# bridge.net
KiCad netlist of a schematic drawn in EAGLE
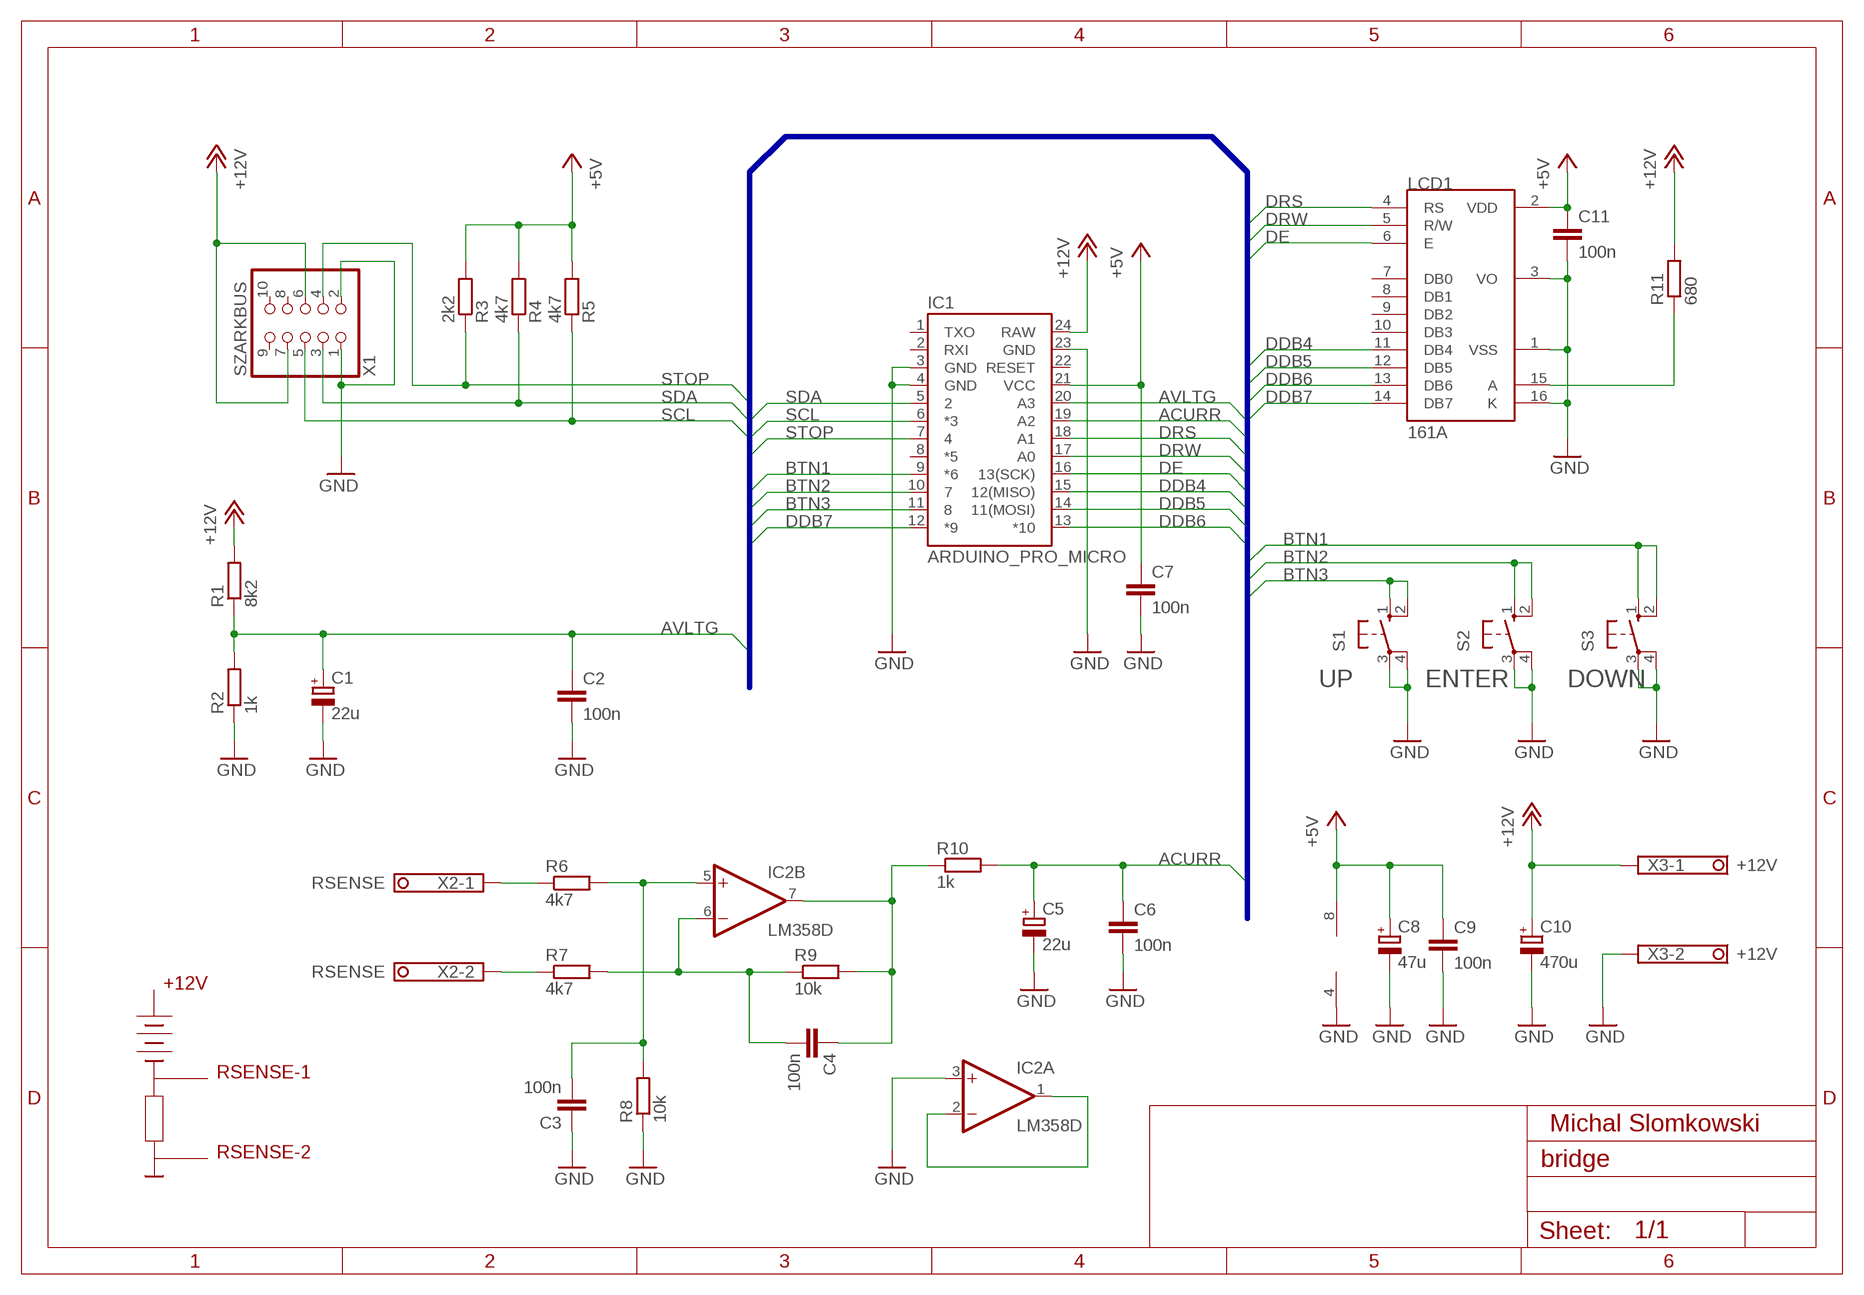
[diagram p0: schematic, sheet 1]

(export (version "E")
  (design (tool "Eeschema 10.0.6"))
  (components
    (comp (ref "C1")
      (value "22u")
      (footprint "eagle-import:B_3528-21W")
      (libsource (lib "eagle-import") (part "CPOL-EUB/3528-21W"))
    )
    (comp (ref "C2")
      (value "100n")
      (footprint "eagle-import:C1206")
      (libsource (lib "eagle-import") (part "C-EUC1206"))
    )
    (comp (ref "C3")
      (value "100n")
      (footprint "eagle-import:C1210")
      (libsource (lib "eagle-import") (part "C-EUC1210"))
    )
    (comp (ref "C4")
      (value "100n")
      (footprint "eagle-import:C1206")
      (libsource (lib "eagle-import") (part "C-EUC1206"))
    )
    (comp (ref "C5")
      (value "22u")
      (footprint "eagle-import:B_3528-21W")
      (libsource (lib "eagle-import") (part "CPOL-EUB/3528-21W"))
    )
    (comp (ref "C6")
      (value "100n")
      (footprint "eagle-import:C1206")
      (libsource (lib "eagle-import") (part "C-EUC1206"))
    )
    (comp (ref "C7")
      (value "100n")
      (footprint "eagle-import:C1206")
      (libsource (lib "eagle-import") (part "C-EUC1206"))
    )
    (comp (ref "C8")
      (value "47u")
      (footprint "eagle-import:C_6032-28W")
      (libsource (lib "eagle-import") (part "CPOL-EUC/6032-28W"))
    )
    (comp (ref "C9")
      (value "100n")
      (footprint "eagle-import:C1206")
      (libsource (lib "eagle-import") (part "C-EUC1206"))
    )
    (comp (ref "C10")
      (value "470u")
      (footprint "eagle-import:E5-8,5")
      (libsource (lib "eagle-import") (part "CPOL-EUE5-8.5"))
    )
    (comp (ref "C11")
      (value "100n")
      (footprint "eagle-import:C1206")
      (libsource (lib "eagle-import") (part "C-EUC1206"))
    )
    (comp (ref "IC1")
      (value "ARDUINO_PRO_MICRO")
      (footprint "eagle-import:ARDUINO_PRO_MICRO")
      (libsource (lib "eagle-import") (part "ARDUINO_PRO_MICRO"))
    )
    (comp (ref "IC2")
      (value "LM358D")
      (footprint "eagle-import:SO08")
      (libsource (lib "eagle-import") (part "LM358D"))
    )
    (comp (ref "LCD1")
      (value "161A")
      (footprint "eagle-import:161A")
      (libsource (lib "eagle-import") (part "161A"))
    )
    (comp (ref "R1")
      (value "8k2")
      (footprint "eagle-import:M1206")
      (libsource (lib "eagle-import") (part "R-EU_M1206"))
    )
    (comp (ref "R2")
      (value "1k")
      (footprint "eagle-import:M1206")
      (libsource (lib "eagle-import") (part "R-EU_M1206"))
    )
    (comp (ref "R3")
      (value "2k2")
      (footprint "eagle-import:M1206")
      (libsource (lib "eagle-import") (part "R-EU_M1206"))
    )
    (comp (ref "R4")
      (value "4k7")
      (footprint "eagle-import:M1206")
      (libsource (lib "eagle-import") (part "R-EU_M1206"))
    )
    (comp (ref "R5")
      (value "4k7")
      (footprint "eagle-import:M1206")
      (libsource (lib "eagle-import") (part "R-EU_M1206"))
    )
    (comp (ref "R6")
      (value "4k7")
      (footprint "eagle-import:M1206")
      (libsource (lib "eagle-import") (part "R-EU_M1206"))
    )
    (comp (ref "R7")
      (value "4k7")
      (footprint "eagle-import:M1206")
      (libsource (lib "eagle-import") (part "R-EU_M1206"))
    )
    (comp (ref "R8")
      (value "10k")
      (footprint "eagle-import:M1206")
      (libsource (lib "eagle-import") (part "R-EU_M1206"))
    )
    (comp (ref "R9")
      (value "10k")
      (footprint "eagle-import:M1206")
      (libsource (lib "eagle-import") (part "R-EU_M1206"))
    )
    (comp (ref "R10")
      (value "1k")
      (footprint "eagle-import:M1206")
      (libsource (lib "eagle-import") (part "R-EU_M1206"))
    )
    (comp (ref "R11")
      (value "680")
      (footprint "eagle-import:0207_12")
      (libsource (lib "eagle-import") (part "R-EU_0207/12"))
    )
    (comp (ref "S1")
      (value "10-XX")
      (footprint "eagle-import:B3F-10XX")
      (fields (field (name "MPN") "B3F-1000"))
      (libsource (lib "eagle-import") (part "10-XX"))
    )
    (comp (ref "S2")
      (value "10-XX")
      (footprint "eagle-import:B3F-10XX")
      (fields (field (name "MPN") "B3F-1000"))
      (libsource (lib "eagle-import") (part "10-XX"))
    )
    (comp (ref "S3")
      (value "10-XX")
      (footprint "eagle-import:B3F-10XX")
      (fields (field (name "MPN") "B3F-1000"))
      (libsource (lib "eagle-import") (part "10-XX"))
    )
    (comp (ref "X1")
      (value "SZARKBUS")
      (footprint "eagle-import:2X05")
      (libsource (lib "eagle-import") (part "PINHD-2X5"))
    )
    (comp (ref "X2")
      (value "RSENSE")
      (footprint "eagle-import:1751248")
      (libsource (lib "eagle-import") (part "1751248"))
    )
    (comp (ref "X3")
      (value "+12V")
      (footprint "eagle-import:1751248")
      (libsource (lib "eagle-import") (part "1751248"))
    )
  )
  (nets
    (net (code "1") (name "+5V") (class "Default")
      (node (ref "C11") (pin "1") (pinfunction "1_1") (pintype "passive"))
      (node (ref "C7") (pin "1") (pinfunction "1_1") (pintype "passive"))
      (node (ref "C8") (pin "+") (pinfunction "+_+") (pintype "passive"))
      (node (ref "C9") (pin "1") (pinfunction "1_1") (pintype "passive"))
      (node (ref "IC1") (pin "21") (pinfunction "VCC_21") (pintype "bidirectional"))
      (node (ref "IC2") (pin "8") (pinfunction "V+_8") (pintype "power_in"))
      (node (ref "LCD1") (pin "2") (pinfunction "VDD_2") (pintype "power_in"))
      (node (ref "R3") (pin "2") (pinfunction "2_2") (pintype "passive"))
      (node (ref "R4") (pin "2") (pinfunction "2_2") (pintype "passive"))
      (node (ref "R5") (pin "2") (pinfunction "2_2") (pintype "passive"))
    )
    (net (code "2") (name "+12V") (class "Default")
      (node (ref "C10") (pin "+") (pinfunction "+_+") (pintype "passive"))
      (node (ref "IC1") (pin "24") (pinfunction "RAW_24") (pintype "bidirectional"))
      (node (ref "R1") (pin "2") (pinfunction "2_2") (pintype "passive"))
      (node (ref "R11") (pin "2") (pinfunction "2_2") (pintype "passive"))
      (node (ref "X1") (pin "6") (pinfunction "6_6") (pintype "passive"))
      (node (ref "X1") (pin "7") (pinfunction "7_7") (pintype "passive"))
      (node (ref "X3") (pin "1") (pinfunction "K_1") (pintype "passive"))
    )
    (net (code "3") (name "/ACURR") (class "Default")
      (node (ref "C5") (pin "+") (pinfunction "+_+") (pintype "passive"))
      (node (ref "C6") (pin "1") (pinfunction "1_1") (pintype "passive"))
      (node (ref "IC1") (pin "19") (pinfunction "A2_19") (pintype "bidirectional"))
      (node (ref "R10") (pin "2") (pinfunction "2_2") (pintype "passive"))
    )
    (net (code "4") (name "/AVLTG") (class "Default")
      (node (ref "C1") (pin "+") (pinfunction "+_+") (pintype "passive"))
      (node (ref "C2") (pin "1") (pinfunction "1_1") (pintype "passive"))
      (node (ref "IC1") (pin "20") (pinfunction "A3_20") (pintype "bidirectional"))
      (node (ref "R1") (pin "1") (pinfunction "1_1") (pintype "passive"))
      (node (ref "R2") (pin "2") (pinfunction "2_2") (pintype "passive"))
    )
    (net (code "5") (name "/BTN1") (class "Default")
      (node (ref "IC1") (pin "9") (pinfunction "*6_9") (pintype "bidirectional"))
      (node (ref "S3") (pin "1") (pinfunction "S_1") (pintype "passive"))
      (node (ref "S3") (pin "2") (pinfunction "S1_2") (pintype "passive"))
    )
    (net (code "6") (name "/BTN2") (class "Default")
      (node (ref "IC1") (pin "10") (pinfunction "7_10") (pintype "bidirectional"))
      (node (ref "S2") (pin "1") (pinfunction "S_1") (pintype "passive"))
      (node (ref "S2") (pin "2") (pinfunction "S1_2") (pintype "passive"))
    )
    (net (code "7") (name "/BTN3") (class "Default")
      (node (ref "IC1") (pin "11") (pinfunction "8_11") (pintype "bidirectional"))
      (node (ref "S1") (pin "1") (pinfunction "S_1") (pintype "passive"))
      (node (ref "S1") (pin "2") (pinfunction "S1_2") (pintype "passive"))
    )
    (net (code "8") (name "/DDB4") (class "Default")
      (node (ref "IC1") (pin "15") (pinfunction "12(MISO)_15") (pintype "bidirectional"))
      (node (ref "LCD1") (pin "11") (pinfunction "DB4_11") (pintype "bidirectional"))
    )
    (net (code "9") (name "/DDB5") (class "Default")
      (node (ref "IC1") (pin "14") (pinfunction "11(MOSI)_14") (pintype "bidirectional"))
      (node (ref "LCD1") (pin "12") (pinfunction "DB5_12") (pintype "bidirectional"))
    )
    (net (code "10") (name "/DDB6") (class "Default")
      (node (ref "IC1") (pin "13") (pinfunction "*10_13") (pintype "bidirectional"))
      (node (ref "LCD1") (pin "13") (pinfunction "DB6_13") (pintype "bidirectional"))
    )
    (net (code "11") (name "/DDB7") (class "Default")
      (node (ref "IC1") (pin "12") (pinfunction "*9_12") (pintype "bidirectional"))
      (node (ref "LCD1") (pin "14") (pinfunction "DB7_14") (pintype "bidirectional"))
    )
    (net (code "12") (name "/DE") (class "Default")
      (node (ref "IC1") (pin "16") (pinfunction "13(SCK)_16") (pintype "bidirectional"))
      (node (ref "LCD1") (pin "6") (pinfunction "E_6") (pintype "bidirectional"))
    )
    (net (code "13") (name "/DRS") (class "Default")
      (node (ref "IC1") (pin "18") (pinfunction "A1_18") (pintype "bidirectional"))
      (node (ref "LCD1") (pin "4") (pinfunction "RS_4") (pintype "bidirectional"))
    )
    (net (code "14") (name "/DRW") (class "Default")
      (node (ref "IC1") (pin "17") (pinfunction "A0_17") (pintype "bidirectional"))
      (node (ref "LCD1") (pin "5") (pinfunction "R/W_5") (pintype "bidirectional"))
    )
    (net (code "15") (name "/SCL") (class "Default")
      (node (ref "IC1") (pin "6") (pinfunction "*3_6") (pintype "bidirectional"))
      (node (ref "R5") (pin "1") (pinfunction "1_1") (pintype "passive"))
      (node (ref "X1") (pin "5") (pinfunction "5_5") (pintype "passive"))
    )
    (net (code "16") (name "/SDA") (class "Default")
      (node (ref "IC1") (pin "5") (pinfunction "2_5") (pintype "bidirectional"))
      (node (ref "R4") (pin "1") (pinfunction "1_1") (pintype "passive"))
      (node (ref "X1") (pin "3") (pinfunction "3_3") (pintype "passive"))
    )
    (net (code "17") (name "/STOP") (class "Default")
      (node (ref "IC1") (pin "7") (pinfunction "4_7") (pintype "bidirectional"))
      (node (ref "R3") (pin "1") (pinfunction "1_1") (pintype "passive"))
      (node (ref "X1") (pin "4") (pinfunction "4_4") (pintype "passive"))
    )
    (net (code "18") (name "GND") (class "Default")
      (node (ref "C1") (pin "-") (pinfunction "-_-") (pintype "passive"))
      (node (ref "C10") (pin "-") (pinfunction "-_-") (pintype "passive"))
      (node (ref "C11") (pin "2") (pinfunction "2_2") (pintype "passive"))
      (node (ref "C2") (pin "2") (pinfunction "2_2") (pintype "passive"))
      (node (ref "C3") (pin "1") (pinfunction "1_1") (pintype "passive"))
      (node (ref "C5") (pin "-") (pinfunction "-_-") (pintype "passive"))
      (node (ref "C6") (pin "2") (pinfunction "2_2") (pintype "passive"))
      (node (ref "C7") (pin "2") (pinfunction "2_2") (pintype "passive"))
      (node (ref "C8") (pin "-") (pinfunction "-_-") (pintype "passive"))
      (node (ref "C9") (pin "2") (pinfunction "2_2") (pintype "passive"))
      (node (ref "IC1") (pin "23") (pinfunction "GND_23") (pintype "bidirectional"))
      (node (ref "IC1") (pin "3") (pinfunction "GND_3") (pintype "bidirectional"))
      (node (ref "IC1") (pin "4") (pinfunction "GND_4") (pintype "bidirectional"))
      (node (ref "IC2") (pin "3") (pinfunction "+IN_3") (pintype "input"))
      (node (ref "IC2") (pin "4") (pinfunction "V-_4") (pintype "power_in"))
      (node (ref "LCD1") (pin "1") (pinfunction "VSS_1") (pintype "power_in"))
      (node (ref "LCD1") (pin "16") (pinfunction "K_16") (pintype "power_in"))
      (node (ref "LCD1") (pin "3") (pinfunction "VO_3") (pintype "input"))
      (node (ref "R2") (pin "1") (pinfunction "1_1") (pintype "passive"))
      (node (ref "R8") (pin "1") (pinfunction "1_1") (pintype "passive"))
      (node (ref "S1") (pin "3") (pinfunction "P_3") (pintype "passive"))
      (node (ref "S1") (pin "4") (pinfunction "P1_4") (pintype "passive"))
      (node (ref "S2") (pin "3") (pinfunction "P_3") (pintype "passive"))
      (node (ref "S2") (pin "4") (pinfunction "P1_4") (pintype "passive"))
      (node (ref "S3") (pin "3") (pinfunction "P_3") (pintype "passive"))
      (node (ref "S3") (pin "4") (pinfunction "P1_4") (pintype "passive"))
      (node (ref "X1") (pin "1") (pinfunction "1_1") (pintype "passive"))
      (node (ref "X1") (pin "2") (pinfunction "2_2") (pintype "passive"))
      (node (ref "X3") (pin "2") (pinfunction "K_2") (pintype "passive"))
    )
    (net (code "19") (name "Net-(IC2A--IN)") (class "Default")
      (node (ref "IC2") (pin "1") (pinfunction "OUT_1") (pintype "output"))
      (node (ref "IC2") (pin "2") (pinfunction "-IN_2") (pintype "input"))
    )
    (net (code "20") (name "Net-(IC2B-+IN)") (class "Default")
      (node (ref "C3") (pin "2") (pinfunction "2_2") (pintype "passive"))
      (node (ref "IC2") (pin "5") (pinfunction "+IN_5") (pintype "input"))
      (node (ref "R6") (pin "2") (pinfunction "2_2") (pintype "passive"))
      (node (ref "R8") (pin "2") (pinfunction "2_2") (pintype "passive"))
    )
    (net (code "21") (name "Net-(IC2B--IN)") (class "Default")
      (node (ref "C4") (pin "2") (pinfunction "2_2") (pintype "passive"))
      (node (ref "IC2") (pin "6") (pinfunction "-IN_6") (pintype "input"))
      (node (ref "R7") (pin "2") (pinfunction "2_2") (pintype "passive"))
      (node (ref "R9") (pin "1") (pinfunction "1_1") (pintype "passive"))
    )
    (net (code "22") (name "Net-(IC2B-OUT)") (class "Default")
      (node (ref "C4") (pin "1") (pinfunction "1_1") (pintype "passive"))
      (node (ref "IC2") (pin "7") (pinfunction "OUT_7") (pintype "output"))
      (node (ref "R10") (pin "1") (pinfunction "1_1") (pintype "passive"))
      (node (ref "R9") (pin "2") (pinfunction "2_2") (pintype "passive"))
    )
    (net (code "23") (name "Net-(LCD1-A)") (class "Default")
      (node (ref "LCD1") (pin "15") (pinfunction "A_15") (pintype "power_in"))
      (node (ref "R11") (pin "1") (pinfunction "1_1") (pintype "passive"))
    )
    (net (code "24") (name "Net-(X2A-K)") (class "Default")
      (node (ref "R6") (pin "1") (pinfunction "1_1") (pintype "passive"))
      (node (ref "X2") (pin "1") (pinfunction "K_1") (pintype "passive"))
    )
    (net (code "25") (name "Net-(X2B-K)") (class "Default")
      (node (ref "R7") (pin "1") (pinfunction "1_1") (pintype "passive"))
      (node (ref "X2") (pin "2") (pinfunction "K_2") (pintype "passive"))
    )
    (net (code "26") (name "unconnected-(IC1-*5-Pad8)") (class "Default")
      (node (ref "IC1") (pin "8") (pinfunction "*5_8") (pintype "bidirectional"))
    )
    (net (code "27") (name "unconnected-(IC1-RESET-Pad22)") (class "Default")
      (node (ref "IC1") (pin "22") (pinfunction "RESET_22") (pintype "bidirectional"))
    )
    (net (code "28") (name "unconnected-(IC1-RXI-Pad2)") (class "Default")
      (node (ref "IC1") (pin "2") (pinfunction "RXI_2") (pintype "bidirectional"))
    )
    (net (code "29") (name "unconnected-(IC1-TXO-Pad1)") (class "Default")
      (node (ref "IC1") (pin "1") (pinfunction "TXO_1") (pintype "bidirectional"))
    )
    (net (code "30") (name "unconnected-(LCD1-DB0-Pad7)") (class "Default")
      (node (ref "LCD1") (pin "7") (pinfunction "DB0_7") (pintype "bidirectional"))
    )
    (net (code "31") (name "unconnected-(LCD1-DB1-Pad8)") (class "Default")
      (node (ref "LCD1") (pin "8") (pinfunction "DB1_8") (pintype "bidirectional"))
    )
    (net (code "32") (name "unconnected-(LCD1-DB2-Pad9)") (class "Default")
      (node (ref "LCD1") (pin "9") (pinfunction "DB2_9") (pintype "bidirectional"))
    )
    (net (code "33") (name "unconnected-(LCD1-DB3-Pad10)") (class "Default")
      (node (ref "LCD1") (pin "10") (pinfunction "DB3_10") (pintype "bidirectional"))
    )
    (net (code "34") (name "unconnected-(X1-Pad8)") (class "Default")
      (node (ref "X1") (pin "8") (pinfunction "8_8") (pintype "passive"))
    )
    (net (code "35") (name "unconnected-(X1-Pad9)") (class "Default")
      (node (ref "X1") (pin "9") (pinfunction "9_9") (pintype "passive"))
    )
    (net (code "36") (name "unconnected-(X1-Pad10)") (class "Default")
      (node (ref "X1") (pin "10") (pinfunction "10_10") (pintype "passive"))
    )
  )
)
